# ProPrj_M0G3507__2025-04-02_2025-7-14_232.net
KiCad netlist of a schematic drawn in EasyEDA Pro
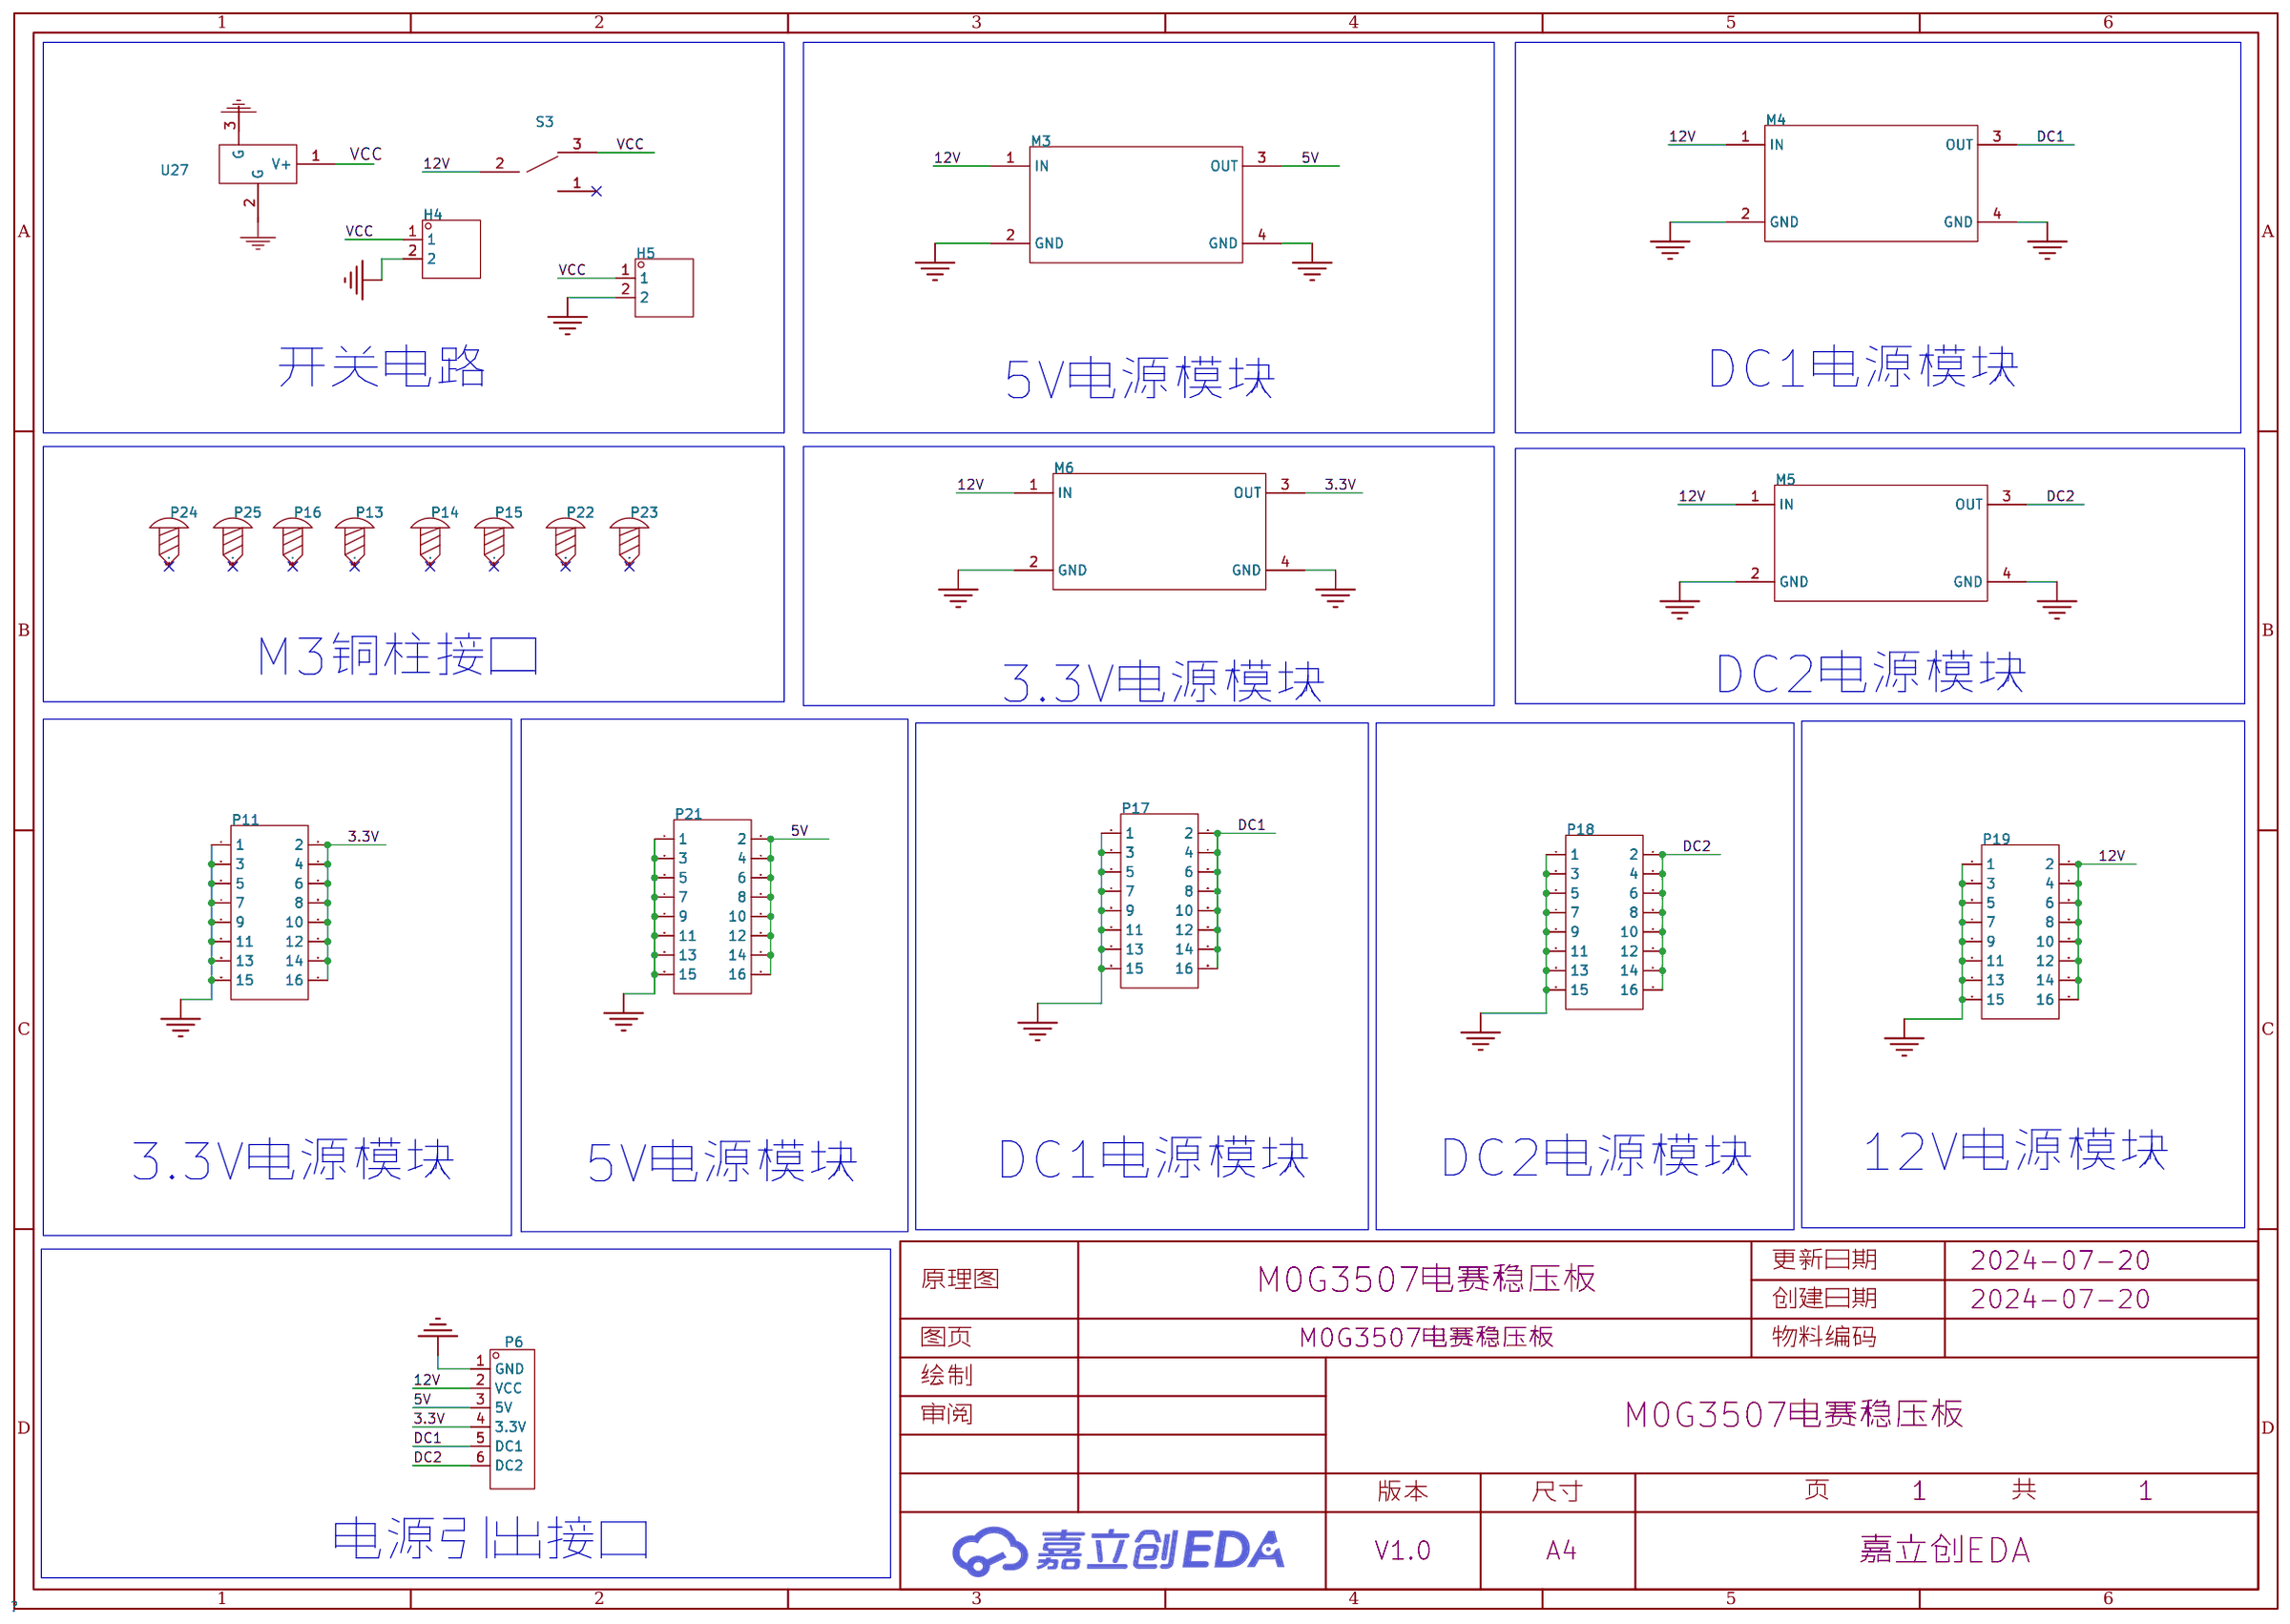
[diagram p0: schematic sheet]

(export (version "E")
  (design (tool "Eeschema 10.0.6"))
  (components
    (comp (ref "H4")
      (value "~")
      (footprint "easyedapro:HDR-TH_2P-P2.54-V-M-1")
      (fields (field (name "Manufacturer Part") "B-2100S02P-A110") (field (name "Manufacturer") "Ckmtw(灿科盟)"))
      (libsource (lib "easyedapro") (part "210S-1*2P L=11.6MMGold-plated black"))
    )
    (comp (ref "H5")
      (value "~")
      (footprint "easyedapro:HDR-TH_2P-P2.54-V-M-1")
      (fields (field (name "Manufacturer Part") "B-2100S02P-A110") (field (name "Manufacturer") "Ckmtw(灿科盟)"))
      (libsource (lib "easyedapro") (part "210S-1*2P L=11.6MMGold-plated black"))
    )
    (comp (ref "M3")
      (value "~")
      (footprint "easyedapro:LM2596稳压模块")
      (description "直流稳压模块LM2596S")
      (libsource (lib "easyedapro") (part "LM2596稳压模块"))
    )
    (comp (ref "M4")
      (value "~")
      (footprint "easyedapro:LM2596稳压模块")
      (description "直流稳压模块LM2596S")
      (libsource (lib "easyedapro") (part "LM2596稳压模块"))
    )
    (comp (ref "M5")
      (value "~")
      (footprint "easyedapro:LM2596稳压模块")
      (description "直流稳压模块LM2596S")
      (libsource (lib "easyedapro") (part "LM2596稳压模块"))
    )
    (comp (ref "M6")
      (value "~")
      (footprint "easyedapro:LM2596稳压模块")
      (description "直流稳压模块LM2596S")
      (libsource (lib "easyedapro") (part "LM2596稳压模块"))
    )
    (comp (ref "P6")
      (value "2.54pitch 6P")
      (footprint "easyedapro:footprint_2943")
      (fields (field (name "Manufacturer Part") "杜邦2.54-6A弯针") (field (name "Manufacturer") "BOOMELE(博穆精密)"))
      (libsource (lib "easyedapro") (part "2.54pitch 6P"))
    )
    (comp (ref "P11")
      (value "2.54-2*8P针")
      (footprint "easyedapro:HDR-TH_16P-P2.54-IO")
      (fields (field (name "Manufacturer") "BOOMELE(博穆精密)"))
      (libsource (lib "easyedapro") (part "2.54-2*8P排针"))
    )
    (comp (ref "P13") (value "~") (footprint "easyedapro:M3螺丝") (libsource (lib "easyedapro") (part "螺丝孔")))
    (comp (ref "P14") (value "~") (footprint "easyedapro:M3螺丝") (libsource (lib "easyedapro") (part "螺丝孔")))
    (comp (ref "P15") (value "~") (footprint "easyedapro:M3螺丝") (libsource (lib "easyedapro") (part "螺丝孔")))
    (comp (ref "P16") (value "~") (footprint "easyedapro:M3螺丝") (libsource (lib "easyedapro") (part "螺丝孔")))
    (comp (ref "P17")
      (value "2.54-2*8P针")
      (footprint "easyedapro:HDR-TH_16P-P2.54-IO")
      (fields (field (name "Manufacturer") "BOOMELE(博穆精密)"))
      (libsource (lib "easyedapro") (part "2.54-2*8P排针"))
    )
    (comp (ref "P18")
      (value "2.54-2*8P针")
      (footprint "easyedapro:HDR-TH_16P-P2.54-IO")
      (fields (field (name "Manufacturer") "BOOMELE(博穆精密)"))
      (libsource (lib "easyedapro") (part "2.54-2*8P排针"))
    )
    (comp (ref "P19")
      (value "2.54-2*8P针")
      (footprint "easyedapro:HDR-TH_16P-P2.54-IO")
      (fields (field (name "Manufacturer") "BOOMELE(博穆精密)"))
      (libsource (lib "easyedapro") (part "2.54-2*8P排针"))
    )
    (comp (ref "P21")
      (value "2.54-2*8P针")
      (footprint "easyedapro:HDR-TH_16P-P2.54-IO")
      (fields (field (name "Manufacturer") "BOOMELE(博穆精密)"))
      (libsource (lib "easyedapro") (part "2.54-2*8P排针"))
    )
    (comp (ref "P22") (value "~") (footprint "easyedapro:M3螺丝") (libsource (lib "easyedapro") (part "螺丝孔")))
    (comp (ref "P23") (value "~") (footprint "easyedapro:M3螺丝") (libsource (lib "easyedapro") (part "螺丝孔")))
    (comp (ref "P24") (value "~") (footprint "easyedapro:M3螺丝") (libsource (lib "easyedapro") (part "螺丝孔")))
    (comp (ref "P25") (value "~") (footprint "easyedapro:M3螺丝") (libsource (lib "easyedapro") (part "螺丝孔")))
    (comp (ref "S3")
      (value "拨动开关")
      (footprint "easyedapro:footprint_4303")
      (fields (field (name "Publisher") "Altium Limited"))
      (libsource (lib "easyedapro") (part "拨动开关"))
    )
    (comp (ref "U27")
      (value "DC母座5.5 2.1")
      (footprint "easyedapro:footprint_a1df")
      (libsource (lib "easyedapro") (part "DC母座5.5 2.1"))
    )
  )
  (nets
    (net (code "1") (name "/3.3V") (class "Default")
      (node (ref "M6") (pin "3") (pinfunction "OUT_3") (pintype "input"))
      (node (ref "P11") (pin "10") (pinfunction "10_10") (pintype "input"))
      (node (ref "P11") (pin "12") (pinfunction "12_12") (pintype "input"))
      (node (ref "P11") (pin "14") (pinfunction "14_14") (pintype "input"))
      (node (ref "P11") (pin "16") (pinfunction "16_16") (pintype "input"))
      (node (ref "P11") (pin "2") (pinfunction "2_2") (pintype "input"))
      (node (ref "P11") (pin "4") (pinfunction "4_4") (pintype "input"))
      (node (ref "P11") (pin "6") (pinfunction "6_6") (pintype "input"))
      (node (ref "P11") (pin "8") (pinfunction "8_8") (pintype "input"))
      (node (ref "P6") (pin "4") (pinfunction "3.3V_4") (pintype "unspecified"))
    )
    (net (code "2") (name "/5V") (class "Default")
      (node (ref "M3") (pin "3") (pinfunction "OUT_3") (pintype "input"))
      (node (ref "P21") (pin "10") (pinfunction "10_10") (pintype "input"))
      (node (ref "P21") (pin "12") (pinfunction "12_12") (pintype "input"))
      (node (ref "P21") (pin "14") (pinfunction "14_14") (pintype "input"))
      (node (ref "P21") (pin "16") (pinfunction "16_16") (pintype "input"))
      (node (ref "P21") (pin "2") (pinfunction "2_2") (pintype "input"))
      (node (ref "P21") (pin "4") (pinfunction "4_4") (pintype "input"))
      (node (ref "P21") (pin "6") (pinfunction "6_6") (pintype "input"))
      (node (ref "P21") (pin "8") (pinfunction "8_8") (pintype "input"))
      (node (ref "P6") (pin "3") (pinfunction "5V_3") (pintype "unspecified"))
    )
    (net (code "3") (name "/12V") (class "Default")
      (node (ref "M3") (pin "1") (pinfunction "IN_1") (pintype "input"))
      (node (ref "M4") (pin "1") (pinfunction "IN_1") (pintype "input"))
      (node (ref "M5") (pin "1") (pinfunction "IN_1") (pintype "input"))
      (node (ref "M6") (pin "1") (pinfunction "IN_1") (pintype "input"))
      (node (ref "P19") (pin "10") (pinfunction "10_10") (pintype "input"))
      (node (ref "P19") (pin "12") (pinfunction "12_12") (pintype "input"))
      (node (ref "P19") (pin "14") (pinfunction "14_14") (pintype "input"))
      (node (ref "P19") (pin "16") (pinfunction "16_16") (pintype "input"))
      (node (ref "P19") (pin "2") (pinfunction "2_2") (pintype "input"))
      (node (ref "P19") (pin "4") (pinfunction "4_4") (pintype "input"))
      (node (ref "P19") (pin "6") (pinfunction "6_6") (pintype "input"))
      (node (ref "P19") (pin "8") (pinfunction "8_8") (pintype "input"))
      (node (ref "P6") (pin "2") (pinfunction "VCC_2") (pintype "unspecified"))
      (node (ref "S3") (pin "2") (pintype "unspecified"))
    )
    (net (code "4") (name "/DC1") (class "Default")
      (node (ref "M4") (pin "3") (pinfunction "OUT_3") (pintype "input"))
      (node (ref "P17") (pin "10") (pinfunction "10_10") (pintype "input"))
      (node (ref "P17") (pin "12") (pinfunction "12_12") (pintype "input"))
      (node (ref "P17") (pin "14") (pinfunction "14_14") (pintype "input"))
      (node (ref "P17") (pin "16") (pinfunction "16_16") (pintype "input"))
      (node (ref "P17") (pin "2") (pinfunction "2_2") (pintype "input"))
      (node (ref "P17") (pin "4") (pinfunction "4_4") (pintype "input"))
      (node (ref "P17") (pin "6") (pinfunction "6_6") (pintype "input"))
      (node (ref "P17") (pin "8") (pinfunction "8_8") (pintype "input"))
      (node (ref "P6") (pin "5") (pinfunction "DC1_5") (pintype "unspecified"))
    )
    (net (code "5") (name "/DC2") (class "Default")
      (node (ref "M5") (pin "3") (pinfunction "OUT_3") (pintype "input"))
      (node (ref "P18") (pin "10") (pinfunction "10_10") (pintype "input"))
      (node (ref "P18") (pin "12") (pinfunction "12_12") (pintype "input"))
      (node (ref "P18") (pin "14") (pinfunction "14_14") (pintype "input"))
      (node (ref "P18") (pin "16") (pinfunction "16_16") (pintype "input"))
      (node (ref "P18") (pin "2") (pinfunction "2_2") (pintype "input"))
      (node (ref "P18") (pin "4") (pinfunction "4_4") (pintype "input"))
      (node (ref "P18") (pin "6") (pinfunction "6_6") (pintype "input"))
      (node (ref "P18") (pin "8") (pinfunction "8_8") (pintype "input"))
      (node (ref "P6") (pin "6") (pinfunction "DC2_6") (pintype "unspecified"))
    )
    (net (code "6") (name "/VCC") (class "Default")
      (node (ref "H4") (pin "1") (pinfunction "1_1") (pintype "input"))
      (node (ref "H5") (pin "1") (pinfunction "1_1") (pintype "input"))
      (node (ref "S3") (pin "3") (pintype "unspecified"))
      (node (ref "U27") (pin "1") (pinfunction "V+_1") (pintype "unspecified"))
    )
    (net (code "7") (name "GND") (class "Default")
      (node (ref "H4") (pin "2") (pinfunction "2_2") (pintype "input"))
      (node (ref "H5") (pin "2") (pinfunction "2_2") (pintype "input"))
      (node (ref "M3") (pin "2") (pinfunction "GND_2") (pintype "input"))
      (node (ref "M3") (pin "4") (pinfunction "GND_4") (pintype "input"))
      (node (ref "M4") (pin "2") (pinfunction "GND_2") (pintype "input"))
      (node (ref "M4") (pin "4") (pinfunction "GND_4") (pintype "input"))
      (node (ref "M5") (pin "2") (pinfunction "GND_2") (pintype "input"))
      (node (ref "M5") (pin "4") (pinfunction "GND_4") (pintype "input"))
      (node (ref "M6") (pin "2") (pinfunction "GND_2") (pintype "input"))
      (node (ref "M6") (pin "4") (pinfunction "GND_4") (pintype "input"))
      (node (ref "P11") (pin "1") (pinfunction "1_1") (pintype "input"))
      (node (ref "P11") (pin "11") (pinfunction "11_11") (pintype "input"))
      (node (ref "P11") (pin "13") (pinfunction "13_13") (pintype "input"))
      (node (ref "P11") (pin "15") (pinfunction "15_15") (pintype "input"))
      (node (ref "P11") (pin "3") (pinfunction "3_3") (pintype "input"))
      (node (ref "P11") (pin "5") (pinfunction "5_5") (pintype "input"))
      (node (ref "P11") (pin "7") (pinfunction "7_7") (pintype "input"))
      (node (ref "P11") (pin "9") (pinfunction "9_9") (pintype "input"))
      (node (ref "P17") (pin "1") (pinfunction "1_1") (pintype "input"))
      (node (ref "P17") (pin "11") (pinfunction "11_11") (pintype "input"))
      (node (ref "P17") (pin "13") (pinfunction "13_13") (pintype "input"))
      (node (ref "P17") (pin "15") (pinfunction "15_15") (pintype "input"))
      (node (ref "P17") (pin "3") (pinfunction "3_3") (pintype "input"))
      (node (ref "P17") (pin "5") (pinfunction "5_5") (pintype "input"))
      (node (ref "P17") (pin "7") (pinfunction "7_7") (pintype "input"))
      (node (ref "P17") (pin "9") (pinfunction "9_9") (pintype "input"))
      (node (ref "P18") (pin "1") (pinfunction "1_1") (pintype "input"))
      (node (ref "P18") (pin "11") (pinfunction "11_11") (pintype "input"))
      (node (ref "P18") (pin "13") (pinfunction "13_13") (pintype "input"))
      (node (ref "P18") (pin "15") (pinfunction "15_15") (pintype "input"))
      (node (ref "P18") (pin "3") (pinfunction "3_3") (pintype "input"))
      (node (ref "P18") (pin "5") (pinfunction "5_5") (pintype "input"))
      (node (ref "P18") (pin "7") (pinfunction "7_7") (pintype "input"))
      (node (ref "P18") (pin "9") (pinfunction "9_9") (pintype "input"))
      (node (ref "P19") (pin "1") (pinfunction "1_1") (pintype "input"))
      (node (ref "P19") (pin "11") (pinfunction "11_11") (pintype "input"))
      (node (ref "P19") (pin "13") (pinfunction "13_13") (pintype "input"))
      (node (ref "P19") (pin "15") (pinfunction "15_15") (pintype "input"))
      (node (ref "P19") (pin "3") (pinfunction "3_3") (pintype "input"))
      (node (ref "P19") (pin "5") (pinfunction "5_5") (pintype "input"))
      (node (ref "P19") (pin "7") (pinfunction "7_7") (pintype "input"))
      (node (ref "P19") (pin "9") (pinfunction "9_9") (pintype "input"))
      (node (ref "P21") (pin "1") (pinfunction "1_1") (pintype "input"))
      (node (ref "P21") (pin "11") (pinfunction "11_11") (pintype "input"))
      (node (ref "P21") (pin "13") (pinfunction "13_13") (pintype "input"))
      (node (ref "P21") (pin "15") (pinfunction "15_15") (pintype "input"))
      (node (ref "P21") (pin "3") (pinfunction "3_3") (pintype "input"))
      (node (ref "P21") (pin "5") (pinfunction "5_5") (pintype "input"))
      (node (ref "P21") (pin "7") (pinfunction "7_7") (pintype "input"))
      (node (ref "P21") (pin "9") (pinfunction "9_9") (pintype "input"))
      (node (ref "P6") (pin "1") (pinfunction "GND_1") (pintype "unspecified"))
      (node (ref "U27") (pin "2") (pinfunction "G_2") (pintype "unspecified"))
      (node (ref "U27") (pin "3") (pinfunction "G_3") (pintype "unspecified"))
    )
    (net (code "8") (name "unconnected-(P13-Pad1)") (class "Default")
      (node (ref "P13") (pin "1") (pinfunction "1_1") (pintype "input+no_connect"))
    )
    (net (code "9") (name "unconnected-(P14-Pad1)") (class "Default")
      (node (ref "P14") (pin "1") (pinfunction "1_1") (pintype "input+no_connect"))
    )
    (net (code "10") (name "unconnected-(P15-Pad1)") (class "Default")
      (node (ref "P15") (pin "1") (pinfunction "1_1") (pintype "input+no_connect"))
    )
    (net (code "11") (name "unconnected-(P16-Pad1)") (class "Default")
      (node (ref "P16") (pin "1") (pinfunction "1_1") (pintype "input+no_connect"))
    )
    (net (code "12") (name "unconnected-(P22-Pad1)") (class "Default")
      (node (ref "P22") (pin "1") (pinfunction "1_1") (pintype "input+no_connect"))
    )
    (net (code "13") (name "unconnected-(P23-Pad1)") (class "Default")
      (node (ref "P23") (pin "1") (pinfunction "1_1") (pintype "input+no_connect"))
    )
    (net (code "14") (name "unconnected-(P24-Pad1)") (class "Default")
      (node (ref "P24") (pin "1") (pinfunction "1_1") (pintype "input+no_connect"))
    )
    (net (code "15") (name "unconnected-(P25-Pad1)") (class "Default")
      (node (ref "P25") (pin "1") (pinfunction "1_1") (pintype "input+no_connect"))
    )
    (net (code "16") (name "unconnected-(S3-Pad1)") (class "Default")
      (node (ref "S3") (pin "1") (pintype "unspecified+no_connect"))
    )
  )
)
